# ServoToolv04.net
KiCad netlist of a schematic drawn in EAGLE
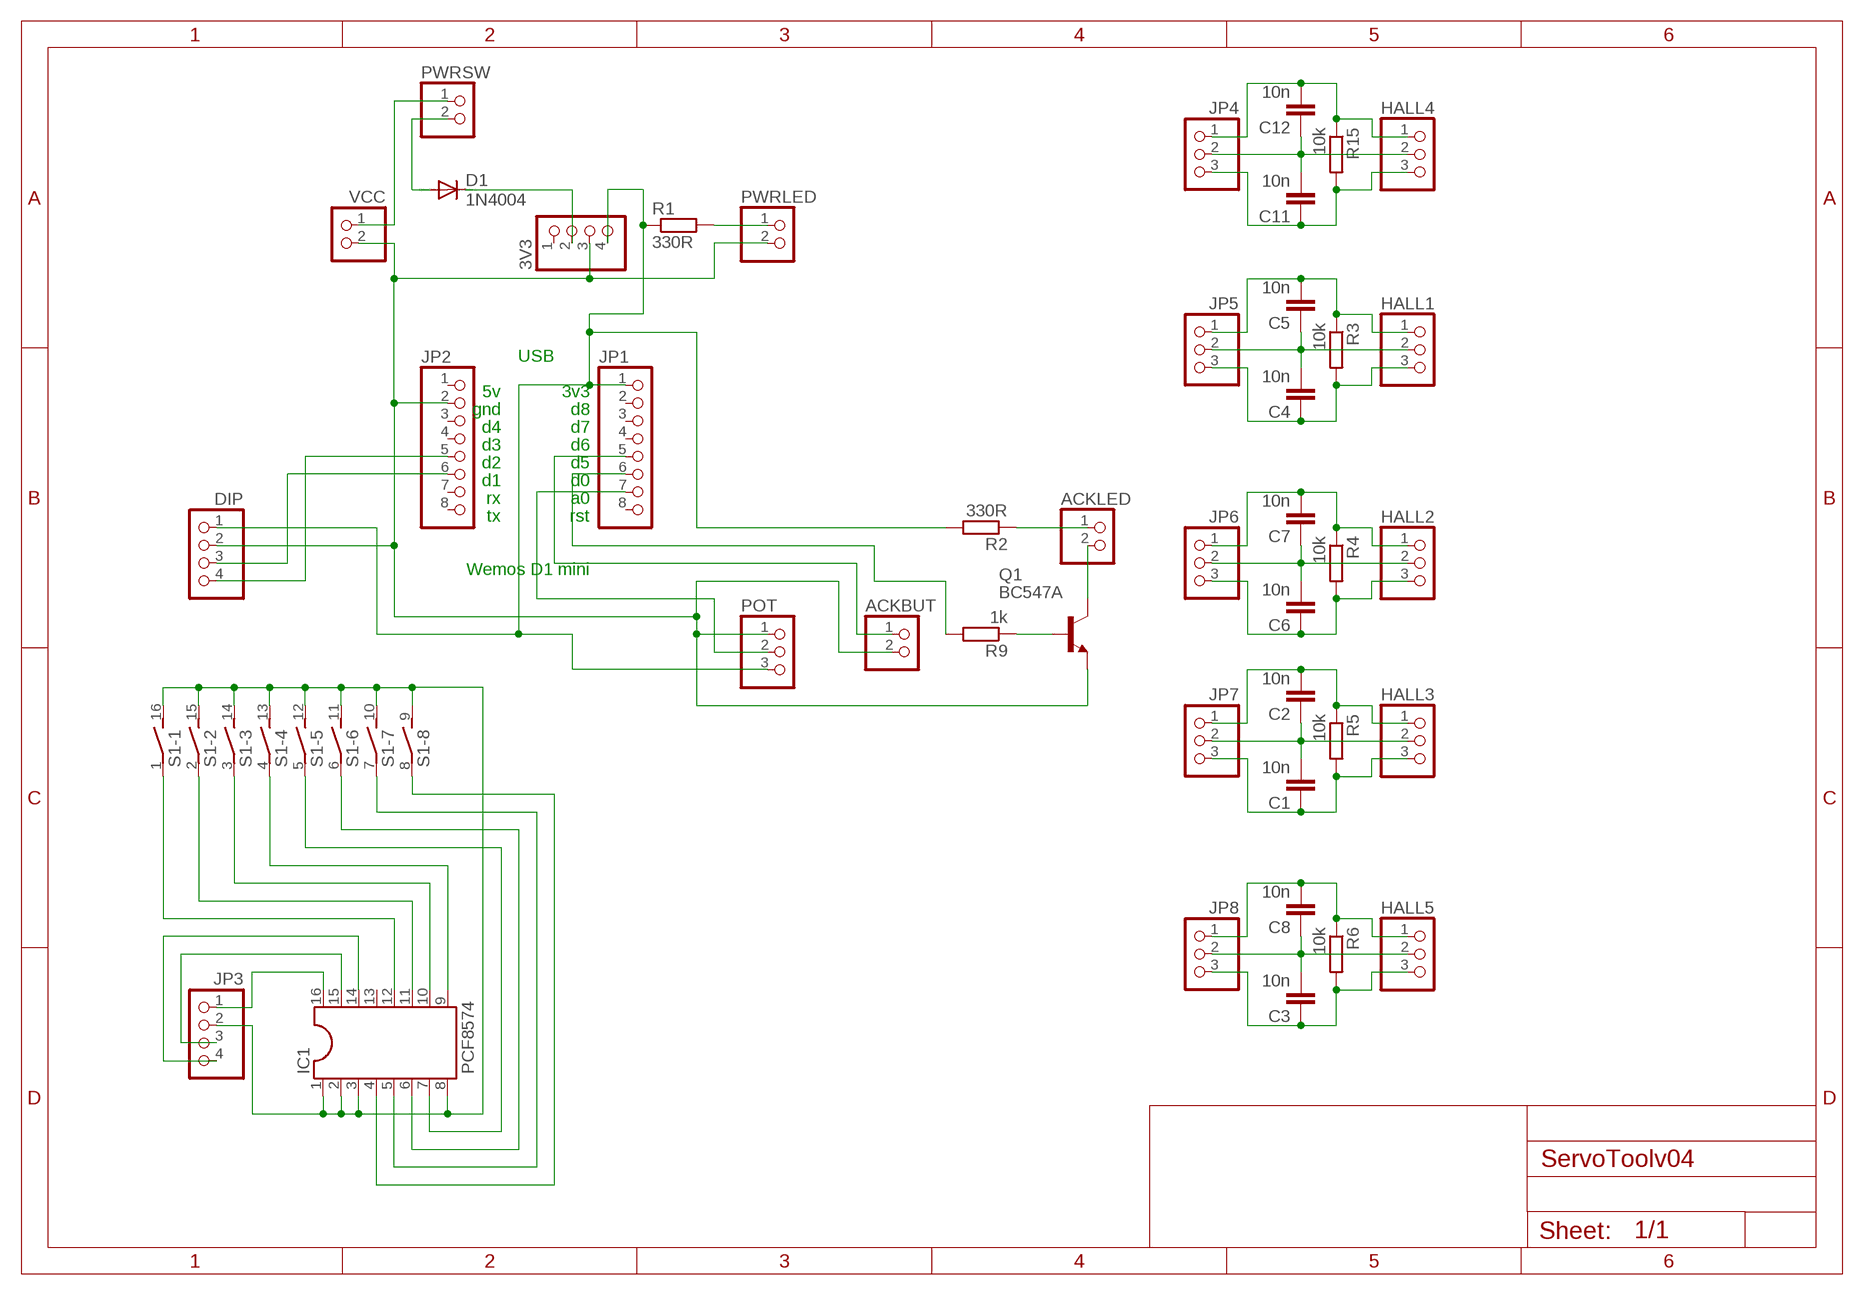
[diagram p0: schematic, sheet 1]

(export (version "E")
  (design (tool "Eeschema 10.0.6"))
  (components
    (comp (ref "3V3")
      (value "PINHD-1X4")
      (footprint "eagle-import:1X04")
      (libsource (lib "eagle-import") (part "PINHD-1X4"))
    )
    (comp (ref "ACKBUT")
      (value "PINHD-1X2/90")
      (footprint "eagle-import:1X02_90")
      (libsource (lib "eagle-import") (part "PINHD-1X2/90"))
    )
    (comp (ref "ACKLED")
      (value "PINHD-1X2/90")
      (footprint "eagle-import:1X02_90")
      (libsource (lib "eagle-import") (part "PINHD-1X2/90"))
    )
    (comp (ref "C1")
      (value "10n")
      (footprint "eagle-import:C050-024X044")
      (libsource (lib "eagle-import") (part "C-EU050-024X044"))
    )
    (comp (ref "C2")
      (value "10n")
      (footprint "eagle-import:C050-024X044")
      (libsource (lib "eagle-import") (part "C-EU050-024X044"))
    )
    (comp (ref "C3")
      (value "10n")
      (footprint "eagle-import:C050-024X044")
      (libsource (lib "eagle-import") (part "C-EU050-024X044"))
    )
    (comp (ref "C4")
      (value "10n")
      (footprint "eagle-import:C050-024X044")
      (libsource (lib "eagle-import") (part "C-EU050-024X044"))
    )
    (comp (ref "C5")
      (value "10n")
      (footprint "eagle-import:C050-024X044")
      (libsource (lib "eagle-import") (part "C-EU050-024X044"))
    )
    (comp (ref "C6")
      (value "10n")
      (footprint "eagle-import:C050-024X044")
      (libsource (lib "eagle-import") (part "C-EU050-024X044"))
    )
    (comp (ref "C7")
      (value "10n")
      (footprint "eagle-import:C050-024X044")
      (libsource (lib "eagle-import") (part "C-EU050-024X044"))
    )
    (comp (ref "C8")
      (value "10n")
      (footprint "eagle-import:C050-024X044")
      (libsource (lib "eagle-import") (part "C-EU050-024X044"))
    )
    (comp (ref "C11")
      (value "10n")
      (footprint "eagle-import:C050-024X044")
      (libsource (lib "eagle-import") (part "C-EU050-024X044"))
    )
    (comp (ref "C12")
      (value "10n")
      (footprint "eagle-import:C050-024X044")
      (libsource (lib "eagle-import") (part "C-EU050-024X044"))
    )
    (comp (ref "D1")
      (value "1N4004")
      (footprint "eagle-import:DO41-10")
      (libsource (lib "eagle-import") (part "1N4004"))
    )
    (comp (ref "DIP")
      (value "PINHD-1X4/90")
      (footprint "eagle-import:1X04_90")
      (libsource (lib "eagle-import") (part "PINHD-1X4/90"))
    )
    (comp (ref "HALL1")
      (value "PINHD-1X3")
      (footprint "eagle-import:1X03")
      (libsource (lib "eagle-import") (part "PINHD-1X3"))
    )
    (comp (ref "HALL2")
      (value "PINHD-1X3")
      (footprint "eagle-import:1X03")
      (libsource (lib "eagle-import") (part "PINHD-1X3"))
    )
    (comp (ref "HALL3")
      (value "PINHD-1X3")
      (footprint "eagle-import:1X03")
      (libsource (lib "eagle-import") (part "PINHD-1X3"))
    )
    (comp (ref "HALL4")
      (value "PINHD-1X3")
      (footprint "eagle-import:1X03")
      (libsource (lib "eagle-import") (part "PINHD-1X3"))
    )
    (comp (ref "HALL5")
      (value "PINHD-1X3")
      (footprint "eagle-import:1X03")
      (libsource (lib "eagle-import") (part "PINHD-1X3"))
    )
    (comp (ref "IC1")
      (value "PCF8574")
      (footprint "eagle-import:DIL16")
      (libsource (lib "eagle-import") (part "DIL16"))
    )
    (comp (ref "JP1")
      (value "PINHD-1X8")
      (footprint "eagle-import:1X08")
      (libsource (lib "eagle-import") (part "PINHD-1X8"))
    )
    (comp (ref "JP2")
      (value "PINHD-1X8")
      (footprint "eagle-import:1X08")
      (libsource (lib "eagle-import") (part "PINHD-1X8"))
    )
    (comp (ref "JP3")
      (value "PINHD-1X4/90")
      (footprint "eagle-import:1X04_90")
      (libsource (lib "eagle-import") (part "PINHD-1X4/90"))
    )
    (comp (ref "JP4")
      (value "PINHD-1X3")
      (footprint "eagle-import:1X03")
      (libsource (lib "eagle-import") (part "PINHD-1X3"))
    )
    (comp (ref "JP5")
      (value "PINHD-1X3")
      (footprint "eagle-import:1X03")
      (libsource (lib "eagle-import") (part "PINHD-1X3"))
    )
    (comp (ref "JP6")
      (value "PINHD-1X3")
      (footprint "eagle-import:1X03")
      (libsource (lib "eagle-import") (part "PINHD-1X3"))
    )
    (comp (ref "JP7")
      (value "PINHD-1X3")
      (footprint "eagle-import:1X03")
      (libsource (lib "eagle-import") (part "PINHD-1X3"))
    )
    (comp (ref "JP8")
      (value "PINHD-1X3")
      (footprint "eagle-import:1X03")
      (libsource (lib "eagle-import") (part "PINHD-1X3"))
    )
    (comp (ref "POT")
      (value "PINHD-1X3/90")
      (footprint "eagle-import:1X03_90")
      (libsource (lib "eagle-import") (part "PINHD-1X3/90"))
    )
    (comp (ref "PWRLED")
      (value "PINHD-1X2/90")
      (footprint "eagle-import:1X02_90")
      (libsource (lib "eagle-import") (part "PINHD-1X2/90"))
    )
    (comp (ref "PWRSW")
      (value "PINHD-1X2/90")
      (footprint "eagle-import:1X02_90")
      (libsource (lib "eagle-import") (part "PINHD-1X2/90"))
    )
    (comp (ref "Q1")
      (value "BC547A")
      (footprint "eagle-import:TO92")
      (libsource (lib "eagle-import") (part "BC547A"))
    )
    (comp (ref "R1")
      (value "330R")
      (footprint "eagle-import:0207_10")
      (libsource (lib "eagle-import") (part "R-EU_0207/10"))
    )
    (comp (ref "R2")
      (value "330R")
      (footprint "eagle-import:0207_10")
      (libsource (lib "eagle-import") (part "R-EU_0207/10"))
    )
    (comp (ref "R3")
      (value "10k")
      (footprint "eagle-import:0309_10")
      (libsource (lib "eagle-import") (part "R-EU_0309/10"))
    )
    (comp (ref "R4")
      (value "10k")
      (footprint "eagle-import:0309_10")
      (libsource (lib "eagle-import") (part "R-EU_0309/10"))
    )
    (comp (ref "R5")
      (value "10k")
      (footprint "eagle-import:0309_10")
      (libsource (lib "eagle-import") (part "R-EU_0309/10"))
    )
    (comp (ref "R6")
      (value "10k")
      (footprint "eagle-import:0309_10")
      (libsource (lib "eagle-import") (part "R-EU_0309/10"))
    )
    (comp (ref "R9")
      (value "1k")
      (footprint "eagle-import:0207_10")
      (libsource (lib "eagle-import") (part "R-EU_0207/10"))
    )
    (comp (ref "R15")
      (value "10k")
      (footprint "eagle-import:0309_10")
      (libsource (lib "eagle-import") (part "R-EU_0309/10"))
    )
    (comp (ref "S1")
      (value "DIP08S")
      (footprint "eagle-import:DIP08S")
      (libsource (lib "eagle-import") (part "DIP08S"))
    )
    (comp (ref "VCC")
      (value "PINHD-1X2/90")
      (footprint "eagle-import:1X02_90")
      (libsource (lib "eagle-import") (part "PINHD-1X2/90"))
    )
  )
  (nets
    (net (code "1") (name "Net-(3V3-Pad2)") (class "Default")
      (node (ref "3V3") (pin "2") (pinfunction "2_2") (pintype "passive"))
      (node (ref "D1") (pin "C") (pinfunction "C_C") (pintype "passive"))
    )
    (net (code "2") (name "Net-(3V3-Pad4)") (class "Default")
      (node (ref "3V3") (pin "4") (pinfunction "4_4") (pintype "passive"))
      (node (ref "DIP") (pin "1") (pinfunction "1_1") (pintype "passive"))
      (node (ref "JP1") (pin "1") (pinfunction "1_1") (pintype "passive"))
      (node (ref "POT") (pin "3") (pinfunction "3_3") (pintype "passive"))
      (node (ref "R1") (pin "1") (pinfunction "1_1") (pintype "passive"))
      (node (ref "R2") (pin "2") (pinfunction "2_2") (pintype "passive"))
    )
    (net (code "3") (name "Net-(ACKBUT-Pad1)") (class "Default")
      (node (ref "ACKBUT") (pin "1") (pinfunction "1_1") (pintype "passive"))
      (node (ref "JP1") (pin "5") (pinfunction "5_5") (pintype "passive"))
    )
    (net (code "4") (name "Net-(ACKLED-Pad1)") (class "Default")
      (node (ref "ACKLED") (pin "1") (pinfunction "1_1") (pintype "passive"))
      (node (ref "R2") (pin "1") (pinfunction "1_1") (pintype "passive"))
    )
    (net (code "5") (name "Net-(C1-Pad1)") (class "Default")
      (node (ref "C1") (pin "1") (pinfunction "1_1") (pintype "passive"))
      (node (ref "HALL3") (pin "3") (pinfunction "3_3") (pintype "passive"))
      (node (ref "JP7") (pin "3") (pinfunction "3_3") (pintype "passive"))
      (node (ref "R5") (pin "2") (pinfunction "2_2") (pintype "passive"))
    )
    (net (code "6") (name "Net-(C1-Pad2)") (class "Default")
      (node (ref "C1") (pin "2") (pinfunction "2_2") (pintype "passive"))
      (node (ref "C2") (pin "1") (pinfunction "1_1") (pintype "passive"))
      (node (ref "HALL3") (pin "2") (pinfunction "2_2") (pintype "passive"))
      (node (ref "JP7") (pin "2") (pinfunction "2_2") (pintype "passive"))
    )
    (net (code "7") (name "Net-(C2-Pad2)") (class "Default")
      (node (ref "C2") (pin "2") (pinfunction "2_2") (pintype "passive"))
      (node (ref "HALL3") (pin "1") (pinfunction "1_1") (pintype "passive"))
      (node (ref "JP7") (pin "1") (pinfunction "1_1") (pintype "passive"))
      (node (ref "R5") (pin "1") (pinfunction "1_1") (pintype "passive"))
    )
    (net (code "8") (name "Net-(C3-Pad1)") (class "Default")
      (node (ref "C3") (pin "1") (pinfunction "1_1") (pintype "passive"))
      (node (ref "HALL5") (pin "3") (pinfunction "3_3") (pintype "passive"))
      (node (ref "JP8") (pin "3") (pinfunction "3_3") (pintype "passive"))
      (node (ref "R6") (pin "2") (pinfunction "2_2") (pintype "passive"))
    )
    (net (code "9") (name "Net-(C3-Pad2)") (class "Default")
      (node (ref "C3") (pin "2") (pinfunction "2_2") (pintype "passive"))
      (node (ref "C8") (pin "1") (pinfunction "1_1") (pintype "passive"))
      (node (ref "HALL5") (pin "2") (pinfunction "2_2") (pintype "passive"))
      (node (ref "JP8") (pin "2") (pinfunction "2_2") (pintype "passive"))
    )
    (net (code "10") (name "Net-(C4-Pad1)") (class "Default")
      (node (ref "C4") (pin "1") (pinfunction "1_1") (pintype "passive"))
      (node (ref "HALL1") (pin "3") (pinfunction "3_3") (pintype "passive"))
      (node (ref "JP5") (pin "3") (pinfunction "3_3") (pintype "passive"))
      (node (ref "R3") (pin "2") (pinfunction "2_2") (pintype "passive"))
    )
    (net (code "11") (name "Net-(C4-Pad2)") (class "Default")
      (node (ref "C4") (pin "2") (pinfunction "2_2") (pintype "passive"))
      (node (ref "C5") (pin "1") (pinfunction "1_1") (pintype "passive"))
      (node (ref "HALL1") (pin "2") (pinfunction "2_2") (pintype "passive"))
      (node (ref "JP5") (pin "2") (pinfunction "2_2") (pintype "passive"))
    )
    (net (code "12") (name "Net-(C5-Pad2)") (class "Default")
      (node (ref "C5") (pin "2") (pinfunction "2_2") (pintype "passive"))
      (node (ref "HALL1") (pin "1") (pinfunction "1_1") (pintype "passive"))
      (node (ref "JP5") (pin "1") (pinfunction "1_1") (pintype "passive"))
      (node (ref "R3") (pin "1") (pinfunction "1_1") (pintype "passive"))
    )
    (net (code "13") (name "Net-(C6-Pad1)") (class "Default")
      (node (ref "C6") (pin "1") (pinfunction "1_1") (pintype "passive"))
      (node (ref "HALL2") (pin "3") (pinfunction "3_3") (pintype "passive"))
      (node (ref "JP6") (pin "3") (pinfunction "3_3") (pintype "passive"))
      (node (ref "R4") (pin "2") (pinfunction "2_2") (pintype "passive"))
    )
    (net (code "14") (name "Net-(C6-Pad2)") (class "Default")
      (node (ref "C6") (pin "2") (pinfunction "2_2") (pintype "passive"))
      (node (ref "C7") (pin "1") (pinfunction "1_1") (pintype "passive"))
      (node (ref "HALL2") (pin "2") (pinfunction "2_2") (pintype "passive"))
      (node (ref "JP6") (pin "2") (pinfunction "2_2") (pintype "passive"))
    )
    (net (code "15") (name "Net-(C7-Pad2)") (class "Default")
      (node (ref "C7") (pin "2") (pinfunction "2_2") (pintype "passive"))
      (node (ref "HALL2") (pin "1") (pinfunction "1_1") (pintype "passive"))
      (node (ref "JP6") (pin "1") (pinfunction "1_1") (pintype "passive"))
      (node (ref "R4") (pin "1") (pinfunction "1_1") (pintype "passive"))
    )
    (net (code "16") (name "Net-(C8-Pad2)") (class "Default")
      (node (ref "C8") (pin "2") (pinfunction "2_2") (pintype "passive"))
      (node (ref "HALL5") (pin "1") (pinfunction "1_1") (pintype "passive"))
      (node (ref "JP8") (pin "1") (pinfunction "1_1") (pintype "passive"))
      (node (ref "R6") (pin "1") (pinfunction "1_1") (pintype "passive"))
    )
    (net (code "17") (name "Net-(C11-Pad1)") (class "Default")
      (node (ref "C11") (pin "1") (pinfunction "1_1") (pintype "passive"))
      (node (ref "HALL4") (pin "3") (pinfunction "3_3") (pintype "passive"))
      (node (ref "JP4") (pin "3") (pinfunction "3_3") (pintype "passive"))
      (node (ref "R15") (pin "2") (pinfunction "2_2") (pintype "passive"))
    )
    (net (code "18") (name "Net-(C11-Pad2)") (class "Default")
      (node (ref "C11") (pin "2") (pinfunction "2_2") (pintype "passive"))
      (node (ref "C12") (pin "1") (pinfunction "1_1") (pintype "passive"))
      (node (ref "HALL4") (pin "2") (pinfunction "2_2") (pintype "passive"))
      (node (ref "JP4") (pin "2") (pinfunction "2_2") (pintype "passive"))
    )
    (net (code "19") (name "Net-(C12-Pad2)") (class "Default")
      (node (ref "C12") (pin "2") (pinfunction "2_2") (pintype "passive"))
      (node (ref "HALL4") (pin "1") (pinfunction "1_1") (pintype "passive"))
      (node (ref "JP4") (pin "1") (pinfunction "1_1") (pintype "passive"))
      (node (ref "R15") (pin "1") (pinfunction "1_1") (pintype "passive"))
    )
    (net (code "20") (name "Net-(D1-PadA)") (class "Default")
      (node (ref "D1") (pin "A") (pinfunction "A_A") (pintype "passive"))
      (node (ref "PWRSW") (pin "2") (pinfunction "2_2") (pintype "passive"))
    )
    (net (code "21") (name "Net-(DIP-Pad3)") (class "Default")
      (node (ref "DIP") (pin "3") (pinfunction "3_3") (pintype "passive"))
      (node (ref "JP2") (pin "6") (pinfunction "6_6") (pintype "passive"))
    )
    (net (code "22") (name "Net-(DIP-Pad4)") (class "Default")
      (node (ref "DIP") (pin "4") (pinfunction "4_4") (pintype "passive"))
      (node (ref "JP2") (pin "5") (pinfunction "5_5") (pintype "passive"))
    )
    (net (code "23") (name "Net-(IC1-Pad12)") (class "Default")
      (node (ref "IC1") (pin "12") (pinfunction "12_12") (pintype "passive"))
      (node (ref "S1") (pin "1") (pinfunction "1_1") (pintype "passive"))
    )
    (net (code "24") (name "Net-(IC1-Pad14)") (class "Default")
      (node (ref "IC1") (pin "14") (pinfunction "14_14") (pintype "passive"))
      (node (ref "JP3") (pin "4") (pinfunction "4_4") (pintype "passive"))
    )
    (net (code "25") (name "Net-(IC1-Pad15)") (class "Default")
      (node (ref "IC1") (pin "15") (pinfunction "15_15") (pintype "passive"))
      (node (ref "JP3") (pin "3") (pinfunction "3_3") (pintype "passive"))
    )
    (net (code "26") (name "Net-(IC1-Pad16)") (class "Default")
      (node (ref "IC1") (pin "16") (pinfunction "16_16") (pintype "passive"))
      (node (ref "JP3") (pin "1") (pinfunction "1_1") (pintype "passive"))
    )
    (net (code "27") (name "Net-(JP1-Pad6)") (class "Default")
      (node (ref "JP1") (pin "6") (pinfunction "6_6") (pintype "passive"))
      (node (ref "R9") (pin "2") (pinfunction "2_2") (pintype "passive"))
    )
    (net (code "28") (name "Net-(JP1-Pad7)") (class "Default")
      (node (ref "JP1") (pin "7") (pinfunction "7_7") (pintype "passive"))
      (node (ref "POT") (pin "2") (pinfunction "2_2") (pintype "passive"))
    )
    (net (code "29") (name "Net-(PWRLED-Pad1)") (class "Default")
      (node (ref "PWRLED") (pin "1") (pinfunction "1_1") (pintype "passive"))
      (node (ref "R1") (pin "2") (pinfunction "2_2") (pintype "passive"))
    )
    (net (code "30") (name "Net-(PWRSW-Pad1)") (class "Default")
      (node (ref "PWRSW") (pin "1") (pinfunction "1_1") (pintype "passive"))
      (node (ref "VCC") (pin "1") (pinfunction "1_1") (pintype "passive"))
    )
    (net (code "31") (name "Net-(Q1-B)") (class "Default")
      (node (ref "Q1") (pin "2") (pinfunction "B_2") (pintype "passive"))
      (node (ref "R9") (pin "1") (pinfunction "1_1") (pintype "passive"))
    )
    (net (code "32") (name "Net-(Q1-C)") (class "Default")
      (node (ref "ACKLED") (pin "2") (pinfunction "2_2") (pintype "passive"))
      (node (ref "Q1") (pin "3") (pinfunction "C_3") (pintype "passive"))
    )
    (net (code "33") (name "Net-(Q1-E)") (class "Default")
      (node (ref "3V3") (pin "3") (pinfunction "3_3") (pintype "passive"))
      (node (ref "ACKBUT") (pin "2") (pinfunction "2_2") (pintype "passive"))
      (node (ref "DIP") (pin "2") (pinfunction "2_2") (pintype "passive"))
      (node (ref "JP2") (pin "2") (pinfunction "2_2") (pintype "passive"))
      (node (ref "POT") (pin "1") (pinfunction "1_1") (pintype "passive"))
      (node (ref "PWRLED") (pin "2") (pinfunction "2_2") (pintype "passive"))
      (node (ref "Q1") (pin "1") (pinfunction "E_1") (pintype "passive"))
      (node (ref "VCC") (pin "2") (pinfunction "2_2") (pintype "passive"))
    )
    (net (code "34") (name "Net-(S1A-2)") (class "Default")
      (node (ref "IC1") (pin "1") (pinfunction "1_1") (pintype "passive"))
      (node (ref "IC1") (pin "2") (pinfunction "2_2") (pintype "passive"))
      (node (ref "IC1") (pin "3") (pinfunction "3_3") (pintype "passive"))
      (node (ref "IC1") (pin "8") (pinfunction "8_8") (pintype "passive"))
      (node (ref "JP3") (pin "2") (pinfunction "2_2") (pintype "passive"))
      (node (ref "S1") (pin "10") (pinfunction "2_10") (pintype "passive"))
      (node (ref "S1") (pin "11") (pinfunction "2_11") (pintype "passive"))
      (node (ref "S1") (pin "12") (pinfunction "2_12") (pintype "passive"))
      (node (ref "S1") (pin "13") (pinfunction "2_13") (pintype "passive"))
      (node (ref "S1") (pin "14") (pinfunction "2_14") (pintype "passive"))
      (node (ref "S1") (pin "15") (pinfunction "2_15") (pintype "passive"))
      (node (ref "S1") (pin "16") (pinfunction "2_16") (pintype "passive"))
      (node (ref "S1") (pin "9") (pinfunction "2_9") (pintype "passive"))
    )
    (net (code "35") (name "Net-(S1B-1)") (class "Default")
      (node (ref "IC1") (pin "11") (pinfunction "11_11") (pintype "passive"))
      (node (ref "S1") (pin "2") (pinfunction "1_2") (pintype "passive"))
    )
    (net (code "36") (name "Net-(S1C-1)") (class "Default")
      (node (ref "IC1") (pin "10") (pinfunction "10_10") (pintype "passive"))
      (node (ref "S1") (pin "3") (pinfunction "1_3") (pintype "passive"))
    )
    (net (code "37") (name "Net-(S1D-1)") (class "Default")
      (node (ref "IC1") (pin "9") (pinfunction "9_9") (pintype "passive"))
      (node (ref "S1") (pin "4") (pinfunction "1_4") (pintype "passive"))
    )
    (net (code "38") (name "Net-(S1E-1)") (class "Default")
      (node (ref "IC1") (pin "7") (pinfunction "7_7") (pintype "passive"))
      (node (ref "S1") (pin "5") (pinfunction "1_5") (pintype "passive"))
    )
    (net (code "39") (name "Net-(S1F-1)") (class "Default")
      (node (ref "IC1") (pin "6") (pinfunction "6_6") (pintype "passive"))
      (node (ref "S1") (pin "6") (pinfunction "1_6") (pintype "passive"))
    )
    (net (code "40") (name "Net-(S1G-1)") (class "Default")
      (node (ref "IC1") (pin "5") (pinfunction "5_5") (pintype "passive"))
      (node (ref "S1") (pin "7") (pinfunction "1_7") (pintype "passive"))
    )
    (net (code "41") (name "Net-(S1H-1)") (class "Default")
      (node (ref "IC1") (pin "4") (pinfunction "4_4") (pintype "passive"))
      (node (ref "S1") (pin "8") (pinfunction "1_8") (pintype "passive"))
    )
    (net (code "42") (name "unconnected-(3V3-Pad1)") (class "Default")
      (node (ref "3V3") (pin "1") (pinfunction "1_1") (pintype "passive"))
    )
    (net (code "43") (name "unconnected-(IC1-Pad13)") (class "Default")
      (node (ref "IC1") (pin "13") (pinfunction "13_13") (pintype "passive"))
    )
    (net (code "44") (name "unconnected-(JP1-Pad2)") (class "Default")
      (node (ref "JP1") (pin "2") (pinfunction "2_2") (pintype "passive"))
    )
    (net (code "45") (name "unconnected-(JP1-Pad3)") (class "Default")
      (node (ref "JP1") (pin "3") (pinfunction "3_3") (pintype "passive"))
    )
    (net (code "46") (name "unconnected-(JP1-Pad4)") (class "Default")
      (node (ref "JP1") (pin "4") (pinfunction "4_4") (pintype "passive"))
    )
    (net (code "47") (name "unconnected-(JP1-Pad8)") (class "Default")
      (node (ref "JP1") (pin "8") (pinfunction "8_8") (pintype "passive"))
    )
    (net (code "48") (name "unconnected-(JP2-Pad1)") (class "Default")
      (node (ref "JP2") (pin "1") (pinfunction "1_1") (pintype "passive"))
    )
    (net (code "49") (name "unconnected-(JP2-Pad3)") (class "Default")
      (node (ref "JP2") (pin "3") (pinfunction "3_3") (pintype "passive"))
    )
    (net (code "50") (name "unconnected-(JP2-Pad4)") (class "Default")
      (node (ref "JP2") (pin "4") (pinfunction "4_4") (pintype "passive"))
    )
    (net (code "51") (name "unconnected-(JP2-Pad7)") (class "Default")
      (node (ref "JP2") (pin "7") (pinfunction "7_7") (pintype "passive"))
    )
    (net (code "52") (name "unconnected-(JP2-Pad8)") (class "Default")
      (node (ref "JP2") (pin "8") (pinfunction "8_8") (pintype "passive"))
    )
  )
)
